# moire_v1_9-100mm.net
KiCad netlist of a schematic drawn in EAGLE
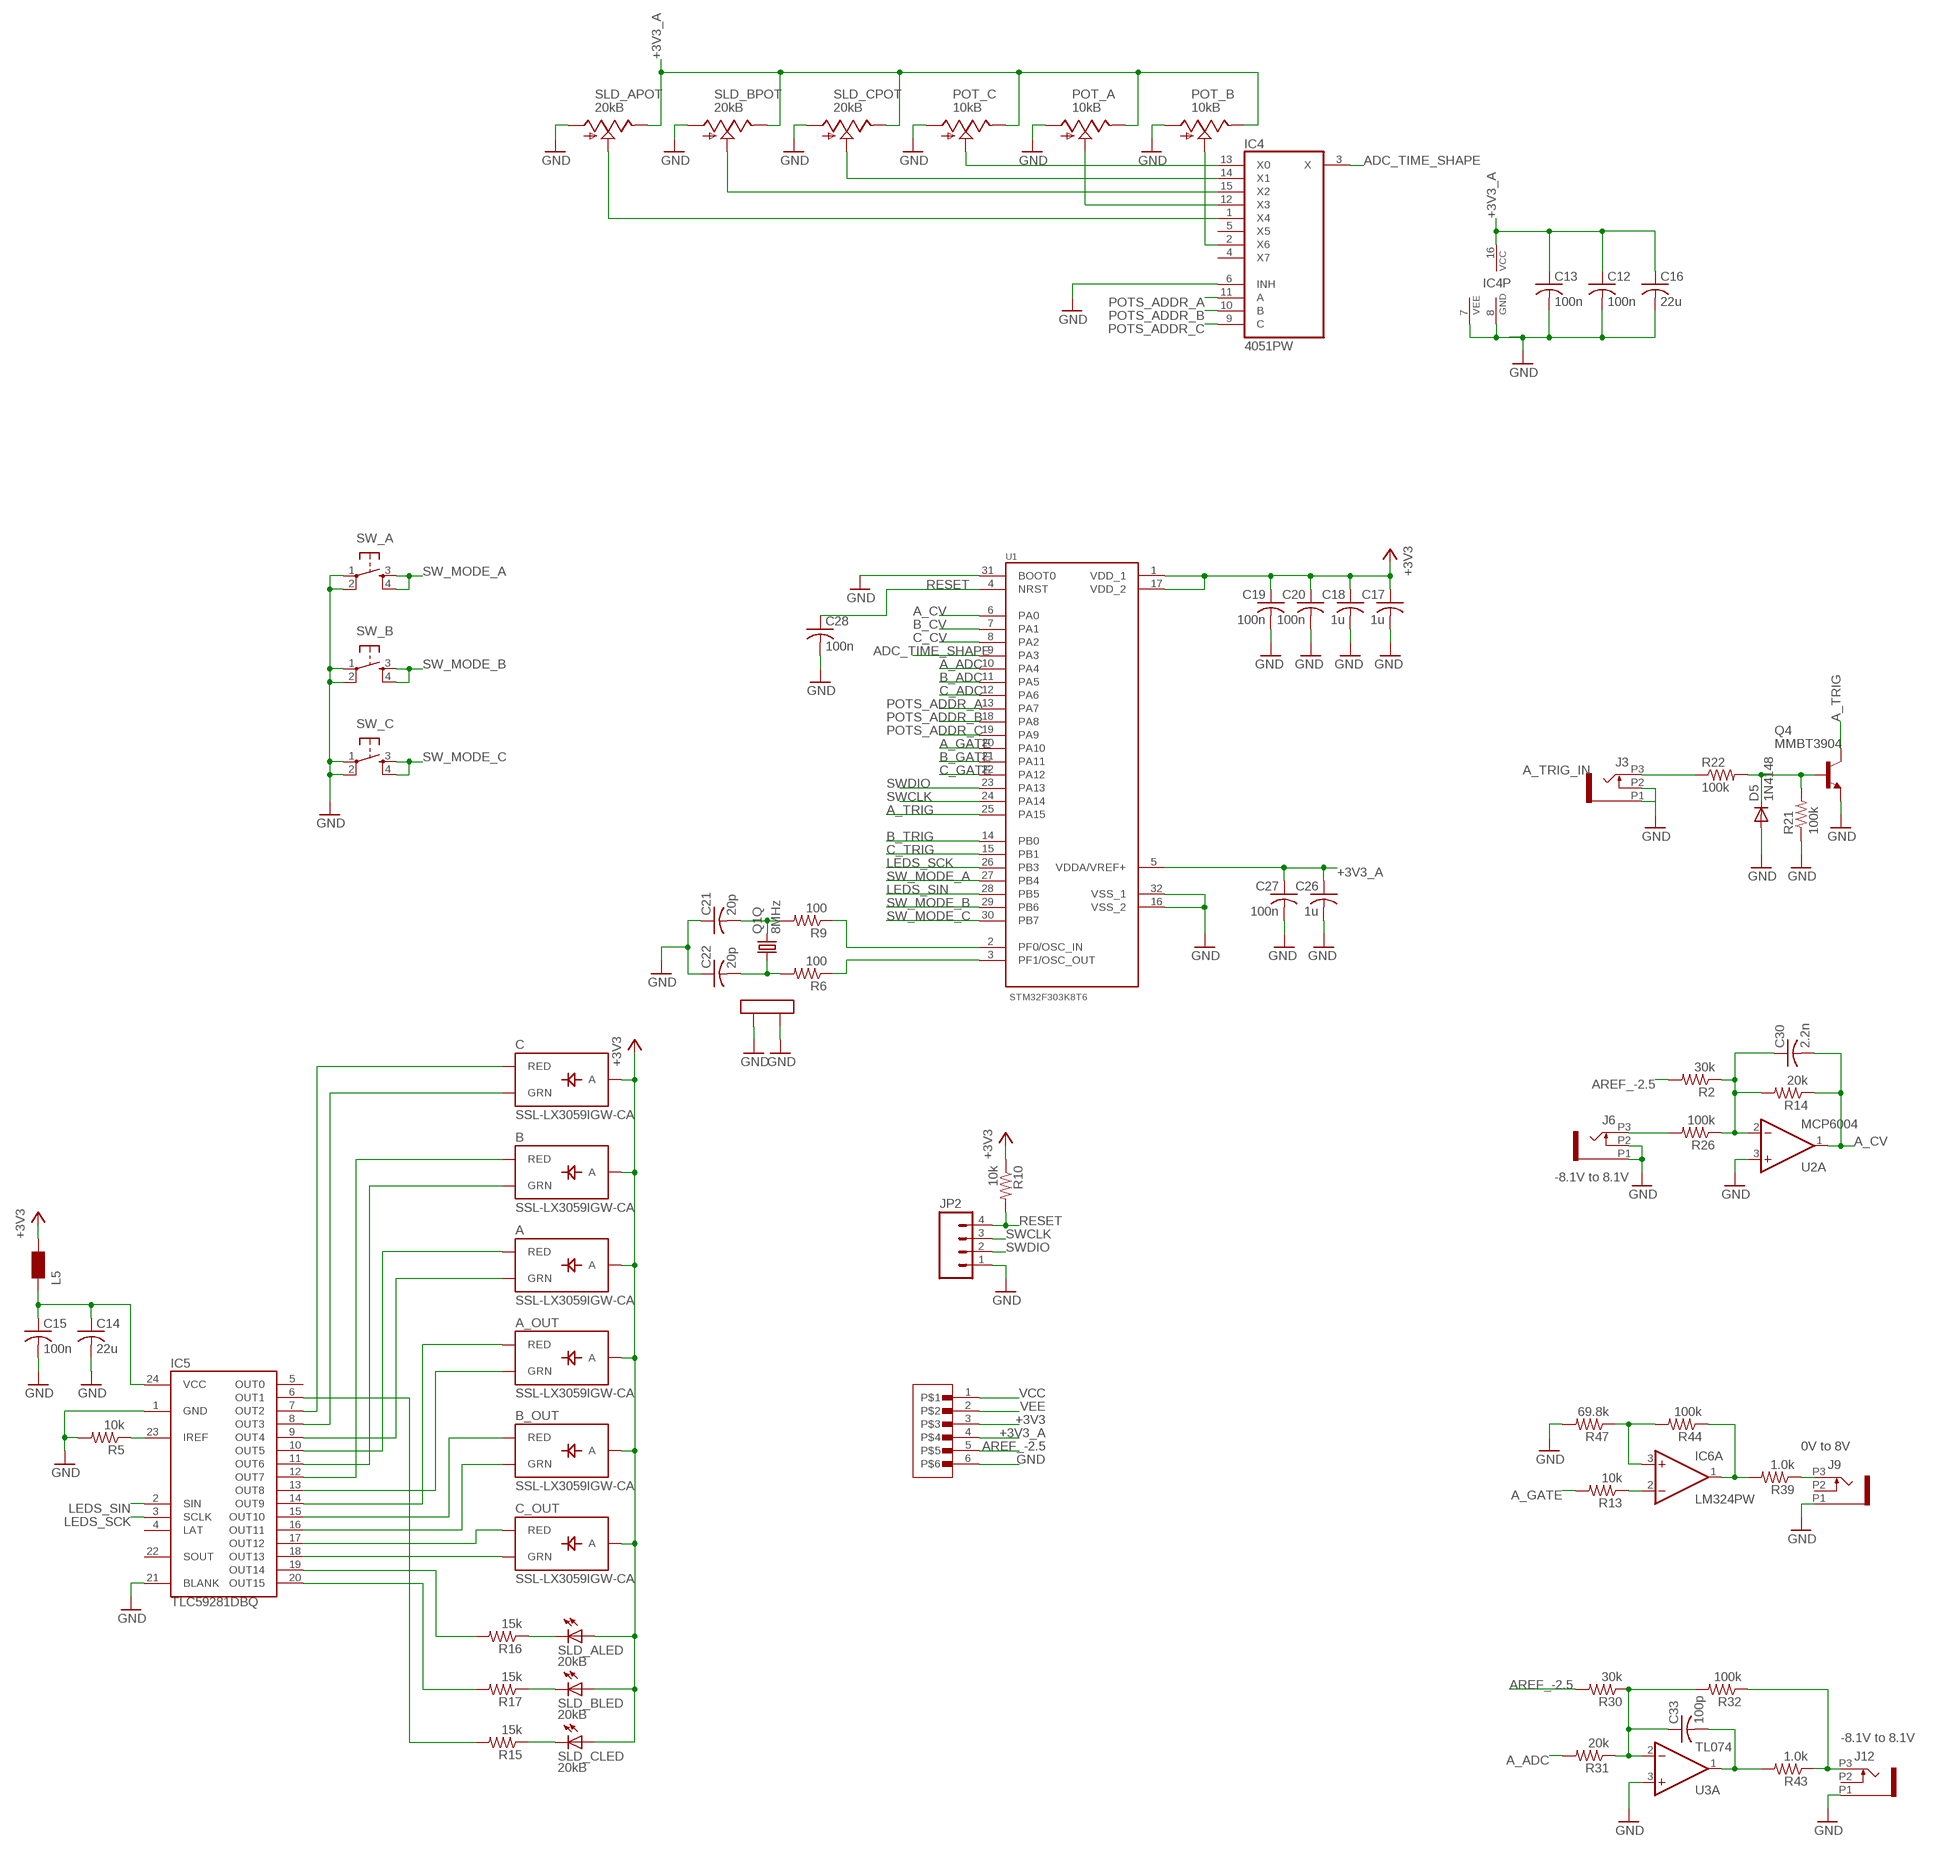
[diagram p0: schematic, sheet 1, part 1 of 2]
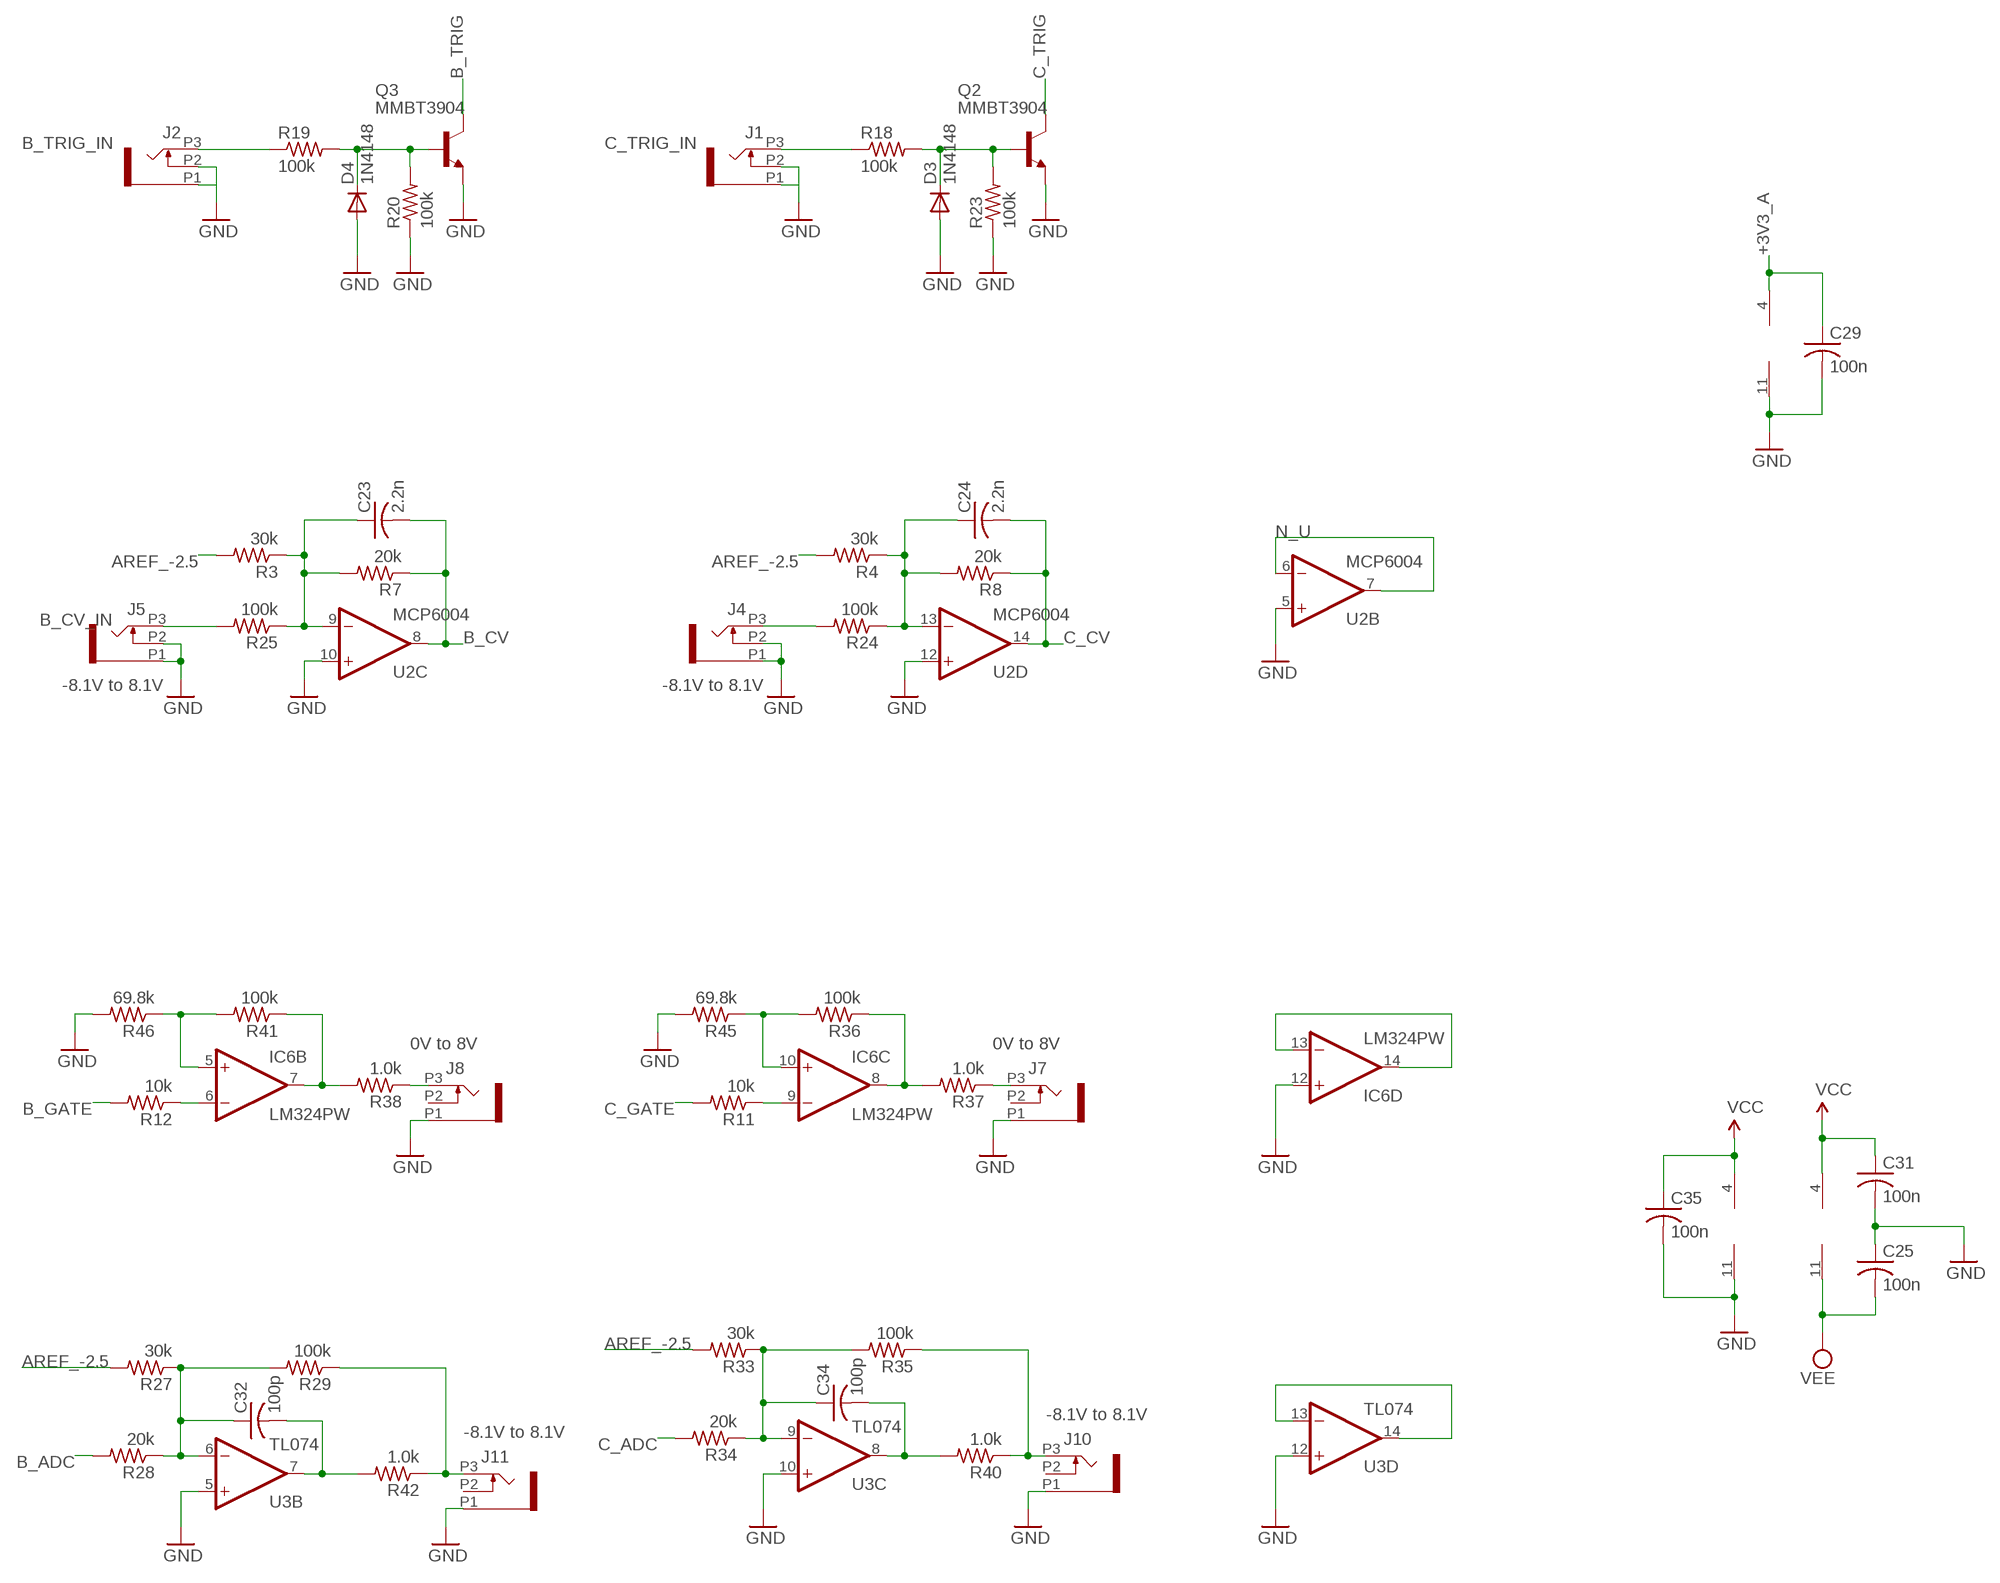
[diagram p1: schematic, sheet 1, part 2 of 2]
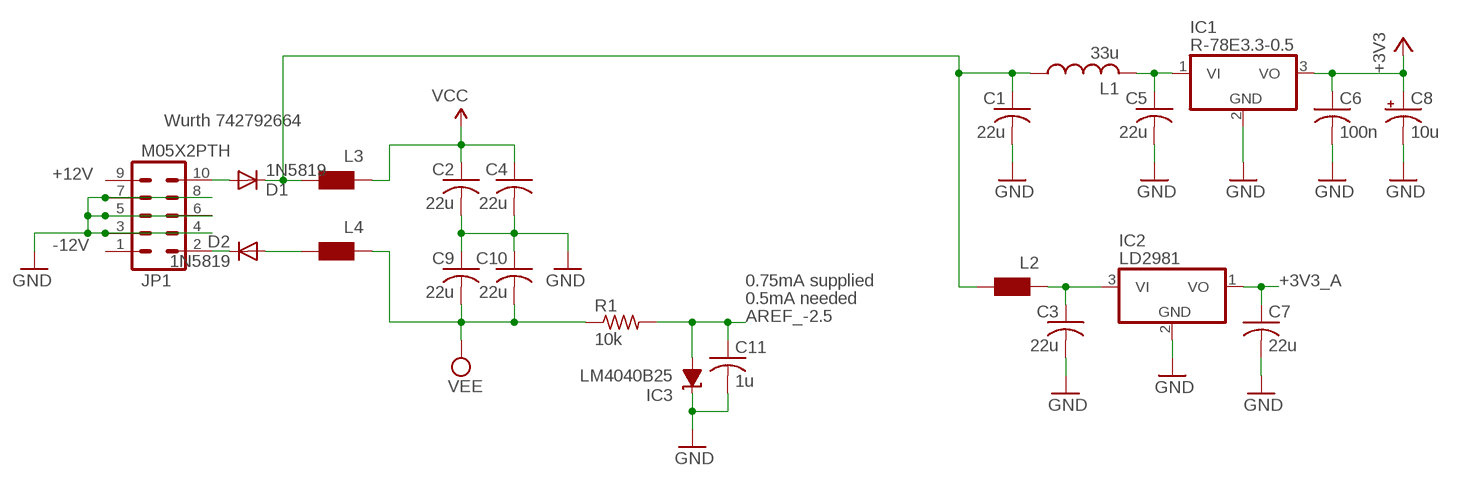
[diagram p2: schematic, sheet 2]

(export (version "E")
  (design (tool "Eeschema 10.0.6"))
  (components
    (comp (ref "C1")
      (value "22u")
      (footprint "eagle-import:RCL_C1206")
      (libsource (lib "eagle-import") (part "RCL_C-USC1206"))
    )
    (comp (ref "C2")
      (value "22u")
      (footprint "eagle-import:RCL_C1206")
      (libsource (lib "eagle-import") (part "RCL_C-USC1206"))
    )
    (comp (ref "C3")
      (value "22u")
      (footprint "eagle-import:RCL_C1206")
      (libsource (lib "eagle-import") (part "RCL_C-USC1206"))
    )
    (comp (ref "C4")
      (value "22u")
      (footprint "eagle-import:RCL_C1206")
      (libsource (lib "eagle-import") (part "RCL_C-USC1206"))
    )
    (comp (ref "C5")
      (value "22u")
      (footprint "eagle-import:RCL_C1206")
      (libsource (lib "eagle-import") (part "RCL_C-USC1206"))
    )
    (comp (ref "C6")
      (value "100n")
      (footprint "eagle-import:RCL_C0603")
      (libsource (lib "eagle-import") (part "RCL_C-USC0603"))
    )
    (comp (ref "C7")
      (value "22u")
      (footprint "eagle-import:RCL_C1206")
      (libsource (lib "eagle-import") (part "RCL_C-USC1206"))
    )
    (comp (ref "C8")
      (value "10u")
      (footprint "eagle-import:RCL_PANASONIC_A")
      (libsource (lib "eagle-import") (part "RCL_CPOL-USA"))
    )
    (comp (ref "C9")
      (value "22u")
      (footprint "eagle-import:RCL_C1206")
      (libsource (lib "eagle-import") (part "RCL_C-USC1206"))
    )
    (comp (ref "C10")
      (value "22u")
      (footprint "eagle-import:RCL_C1206")
      (libsource (lib "eagle-import") (part "RCL_C-USC1206"))
    )
    (comp (ref "C11")
      (value "1u")
      (footprint "eagle-import:RCL_C0603")
      (libsource (lib "eagle-import") (part "RCL_C-USC0603"))
    )
    (comp (ref "D1")
      (value "1N5819")
      (footprint "eagle-import:DIODE_SOD123")
      (libsource (lib "eagle-import") (part "DIODE_DIODE-SOD123"))
    )
    (comp (ref "D2")
      (value "1N5819")
      (footprint "eagle-import:DIODE_SOD123")
      (libsource (lib "eagle-import") (part "DIODE_DIODE-SOD123"))
    )
    (comp (ref "IC1")
      (value "R-78E3.3-0.5")
      (footprint "eagle-import:WE78")
      (libsource (lib "eagle-import") (part "WE173950378"))
    )
    (comp (ref "IC2")
      (value "LD2981")
      (footprint "eagle-import:SOT89")
      (libsource (lib "eagle-import") (part "LD2981ABU"))
    )
    (comp (ref "IC3")
      (value "LM4040B25")
      (footprint "eagle-import:DBZ_R-PDSO-G3")
      (libsource (lib "eagle-import") (part "LM4041DBZB12"))
    )
    (comp (ref "JP1")
      (value "M05X2PTH")
      (footprint "eagle-import:2X5-PTH")
      (libsource (lib "eagle-import") (part "M05X2PTH"))
    )
    (comp (ref "L1")
      (value "33u")
      (footprint "eagle-import:L2012C")
      (libsource (lib "eagle-import") (part "L-USL2012C"))
    )
    (comp (ref "L2")
      (value "WE-CBF_0603")
      (footprint "eagle-import:0603")
      (libsource (lib "eagle-import") (part "WE-CBF_0603"))
    )
    (comp (ref "L3")
      (value "WE-CBF_0603")
      (footprint "eagle-import:0603")
      (libsource (lib "eagle-import") (part "WE-CBF_0603"))
    )
    (comp (ref "L4")
      (value "WE-CBF_0603")
      (footprint "eagle-import:0603")
      (libsource (lib "eagle-import") (part "WE-CBF_0603"))
    )
    (comp (ref "R1")
      (value "10k")
      (footprint "eagle-import:RCL_R0603")
      (libsource (lib "eagle-import") (part "RCL_R-US_R0603"))
    )
    (comp (ref "A")
      (value "SSL-LX3059IGW-CA")
      (footprint "eagle-import:LED-BICOLOR-THROUGHHOLE-LUMEX")
      (libsource (lib "eagle-import") (part "LED-BICOLOR-THROUGHHOLE-CA"))
    )
    (comp (ref "A_OUT")
      (value "SSL-LX3059IGW-CA")
      (footprint "eagle-import:LED-BICOLOR-THROUGHHOLE-LUMEX")
      (libsource (lib "eagle-import") (part "LED-BICOLOR-THROUGHHOLE-CA"))
    )
    (comp (ref "B")
      (value "SSL-LX3059IGW-CA")
      (footprint "eagle-import:LED-BICOLOR-THROUGHHOLE-LUMEX")
      (libsource (lib "eagle-import") (part "LED-BICOLOR-THROUGHHOLE-CA"))
    )
    (comp (ref "B_OUT")
      (value "SSL-LX3059IGW-CA")
      (footprint "eagle-import:LED-BICOLOR-THROUGHHOLE-LUMEX")
      (libsource (lib "eagle-import") (part "LED-BICOLOR-THROUGHHOLE-CA"))
    )
    (comp (ref "C")
      (value "SSL-LX3059IGW-CA")
      (footprint "eagle-import:LED-BICOLOR-THROUGHHOLE-LUMEX")
      (libsource (lib "eagle-import") (part "LED-BICOLOR-THROUGHHOLE-CA"))
    )
    (comp (ref "C12")
      (value "100n")
      (footprint "eagle-import:RCL_C0603")
      (libsource (lib "eagle-import") (part "RCL_C-USC0603"))
    )
    (comp (ref "C13")
      (value "100n")
      (footprint "eagle-import:RCL_C0603")
      (libsource (lib "eagle-import") (part "RCL_C-USC0603"))
    )
    (comp (ref "C14")
      (value "22u")
      (footprint "eagle-import:RCL_C1206")
      (libsource (lib "eagle-import") (part "RCL_C-USC1206"))
    )
    (comp (ref "C15")
      (value "100n")
      (footprint "eagle-import:RCL_C0603")
      (libsource (lib "eagle-import") (part "RCL_C-USC0603"))
    )
    (comp (ref "C16")
      (value "22u")
      (footprint "eagle-import:RCL_C1206")
      (libsource (lib "eagle-import") (part "RCL_C-USC1206"))
    )
    (comp (ref "C17")
      (value "1u")
      (footprint "eagle-import:RCL_C0603")
      (libsource (lib "eagle-import") (part "RCL_C-USC0603"))
    )
    (comp (ref "C18")
      (value "1u")
      (footprint "eagle-import:RCL_C0603")
      (libsource (lib "eagle-import") (part "RCL_C-USC0603"))
    )
    (comp (ref "C19")
      (value "100n")
      (footprint "eagle-import:RCL_C0603")
      (libsource (lib "eagle-import") (part "RCL_C-USC0603"))
    )
    (comp (ref "C20")
      (value "100n")
      (footprint "eagle-import:RCL_C0603")
      (libsource (lib "eagle-import") (part "RCL_C-USC0603"))
    )
    (comp (ref "C21")
      (value "20p")
      (footprint "eagle-import:RCL_C0603")
      (libsource (lib "eagle-import") (part "RCL_C-USC0603"))
    )
    (comp (ref "C22")
      (value "20p")
      (footprint "eagle-import:RCL_C0603")
      (libsource (lib "eagle-import") (part "RCL_C-USC0603"))
    )
    (comp (ref "C23")
      (value "2.2n")
      (footprint "eagle-import:RCL_C0603")
      (libsource (lib "eagle-import") (part "RCL_C-USC0603"))
    )
    (comp (ref "C24")
      (value "2.2n")
      (footprint "eagle-import:RCL_C0603")
      (libsource (lib "eagle-import") (part "RCL_C-USC0603"))
    )
    (comp (ref "C25")
      (value "100n")
      (footprint "eagle-import:RCL_C0603")
      (libsource (lib "eagle-import") (part "RCL_C-USC0603"))
    )
    (comp (ref "C26")
      (value "1u")
      (footprint "eagle-import:RCL_C0603")
      (libsource (lib "eagle-import") (part "RCL_C-USC0603"))
    )
    (comp (ref "C27")
      (value "100n")
      (footprint "eagle-import:RCL_C0603")
      (libsource (lib "eagle-import") (part "RCL_C-USC0603"))
    )
    (comp (ref "C28")
      (value "100n")
      (footprint "eagle-import:RCL_C0603")
      (libsource (lib "eagle-import") (part "RCL_C-USC0603"))
    )
    (comp (ref "C29")
      (value "100n")
      (footprint "eagle-import:RCL_C0603")
      (libsource (lib "eagle-import") (part "RCL_C-USC0603"))
    )
    (comp (ref "C30")
      (value "2.2n")
      (footprint "eagle-import:RCL_C0603")
      (libsource (lib "eagle-import") (part "RCL_C-USC0603"))
    )
    (comp (ref "C31")
      (value "100n")
      (footprint "eagle-import:RCL_C0603")
      (libsource (lib "eagle-import") (part "RCL_C-USC0603"))
    )
    (comp (ref "C32")
      (value "100p")
      (footprint "eagle-import:RCL_C0603")
      (libsource (lib "eagle-import") (part "RCL_C-USC0603"))
    )
    (comp (ref "C33")
      (value "100p")
      (footprint "eagle-import:RCL_C0603")
      (libsource (lib "eagle-import") (part "RCL_C-USC0603"))
    )
    (comp (ref "C34")
      (value "100p")
      (footprint "eagle-import:RCL_C0603")
      (libsource (lib "eagle-import") (part "RCL_C-USC0603"))
    )
    (comp (ref "C35")
      (value "100n")
      (footprint "eagle-import:RCL_C0603")
      (libsource (lib "eagle-import") (part "RCL_C-USC0603"))
    )
    (comp (ref "C_OUT")
      (value "SSL-LX3059IGW-CA")
      (footprint "eagle-import:LED-BICOLOR-THROUGHHOLE-LUMEX")
      (libsource (lib "eagle-import") (part "LED-BICOLOR-THROUGHHOLE-CA"))
    )
    (comp (ref "D3")
      (value "1N4148")
      (footprint "eagle-import:DIODE_SOD523")
      (libsource (lib "eagle-import") (part "DIODE_DIODE-SOD523"))
    )
    (comp (ref "D4")
      (value "1N4148")
      (footprint "eagle-import:DIODE_SOD523")
      (libsource (lib "eagle-import") (part "DIODE_DIODE-SOD523"))
    )
    (comp (ref "D5")
      (value "1N4148")
      (footprint "eagle-import:DIODE_SOD523")
      (libsource (lib "eagle-import") (part "DIODE_DIODE-SOD523"))
    )
    (comp (ref "IC4")
      (value "4051PW")
      (footprint "eagle-import:TSSOP16_065")
      (libsource (lib "eagle-import") (part "4051PW"))
    )
    (comp (ref "IC5")
      (value "TLC59281DBQ")
      (footprint "eagle-import:TSSOP24_0635")
      (libsource (lib "eagle-import") (part "TLC59281DBQ"))
    )
    (comp (ref "IC6")
      (value "LM324PW")
      (footprint "eagle-import:TSSOP14_065")
      (libsource (lib "eagle-import") (part "TL074PW"))
    )
    (comp (ref "J1")
      (value "PJ301_THONKICONN6")
      (footprint "eagle-import:WQP_PJ_301M6")
      (libsource (lib "eagle-import") (part "PJ301_THONKICONN6"))
    )
    (comp (ref "J2")
      (value "PJ301_THONKICONN6")
      (footprint "eagle-import:WQP_PJ_301M6")
      (libsource (lib "eagle-import") (part "PJ301_THONKICONN6"))
    )
    (comp (ref "J3")
      (value "PJ301_THONKICONN6")
      (footprint "eagle-import:WQP_PJ_301M6")
      (libsource (lib "eagle-import") (part "PJ301_THONKICONN6"))
    )
    (comp (ref "J4")
      (value "PJ301_THONKICONN6")
      (footprint "eagle-import:WQP_PJ_301M6")
      (libsource (lib "eagle-import") (part "PJ301_THONKICONN6"))
    )
    (comp (ref "J5")
      (value "PJ301_THONKICONN6")
      (footprint "eagle-import:WQP_PJ_301M6")
      (libsource (lib "eagle-import") (part "PJ301_THONKICONN6"))
    )
    (comp (ref "J6")
      (value "PJ301_THONKICONN6")
      (footprint "eagle-import:WQP_PJ_301M6")
      (libsource (lib "eagle-import") (part "PJ301_THONKICONN6"))
    )
    (comp (ref "J7")
      (value "PJ301_THONKICONN6")
      (footprint "eagle-import:WQP_PJ_301M6")
      (libsource (lib "eagle-import") (part "PJ301_THONKICONN6"))
    )
    (comp (ref "J8")
      (value "PJ301_THONKICONN6")
      (footprint "eagle-import:WQP_PJ_301M6")
      (libsource (lib "eagle-import") (part "PJ301_THONKICONN6"))
    )
    (comp (ref "J9")
      (value "PJ301_THONKICONN6")
      (footprint "eagle-import:WQP_PJ_301M6")
      (libsource (lib "eagle-import") (part "PJ301_THONKICONN6"))
    )
    (comp (ref "J10")
      (value "PJ301_THONKICONN6")
      (footprint "eagle-import:WQP_PJ_301M6")
      (libsource (lib "eagle-import") (part "PJ301_THONKICONN6"))
    )
    (comp (ref "J11")
      (value "PJ301_THONKICONN6")
      (footprint "eagle-import:WQP_PJ_301M6")
      (libsource (lib "eagle-import") (part "PJ301_THONKICONN6"))
    )
    (comp (ref "J12")
      (value "PJ301_THONKICONN6")
      (footprint "eagle-import:WQP_PJ_301M6")
      (libsource (lib "eagle-import") (part "PJ301_THONKICONN6"))
    )
    (comp (ref "JP2")
      (value "M04PTH")
      (footprint "eagle-import:1X04")
      (libsource (lib "eagle-import") (part "M04PTH"))
    )
    (comp (ref "L5")
      (value "WE-CBF_0603")
      (footprint "eagle-import:0603")
      (libsource (lib "eagle-import") (part "WE-CBF_0603"))
    )
    (comp (ref "POT_A")
      (value "10kB")
      (footprint "eagle-import:ALPS_POT_VERTICAL")
      (libsource (lib "eagle-import") (part "POT_USVERTICAL"))
    )
    (comp (ref "POT_B")
      (value "10kB")
      (footprint "eagle-import:ALPS_POT_VERTICAL")
      (libsource (lib "eagle-import") (part "POT_USVERTICAL"))
    )
    (comp (ref "POT_C")
      (value "10kB")
      (footprint "eagle-import:ALPS_POT_VERTICAL")
      (libsource (lib "eagle-import") (part "POT_USVERTICAL"))
    )
    (comp (ref "Q1")
      (value "8MHz")
      (footprint "eagle-import:CTS406")
      (libsource (lib "eagle-import") (part "CRYSTAL"))
    )
    (comp (ref "Q2")
      (value "MMBT3904")
      (footprint "eagle-import:SOT23-BEC")
      (libsource (lib "eagle-import") (part "-NPN-SOT23-BECMMBT3904LT1"))
    )
    (comp (ref "Q3")
      (value "MMBT3904")
      (footprint "eagle-import:SOT23-BEC")
      (libsource (lib "eagle-import") (part "-NPN-SOT23-BECMMBT3904LT1"))
    )
    (comp (ref "Q4")
      (value "MMBT3904")
      (footprint "eagle-import:SOT23-BEC")
      (libsource (lib "eagle-import") (part "-NPN-SOT23-BECMMBT3904LT1"))
    )
    (comp (ref "R2")
      (value "30k")
      (footprint "eagle-import:RCL_R0603")
      (libsource (lib "eagle-import") (part "RCL_R-US_R0603"))
    )
    (comp (ref "R3")
      (value "30k")
      (footprint "eagle-import:RCL_R0603")
      (libsource (lib "eagle-import") (part "RCL_R-US_R0603"))
    )
    (comp (ref "R4")
      (value "30k")
      (footprint "eagle-import:RCL_R0603")
      (libsource (lib "eagle-import") (part "RCL_R-US_R0603"))
    )
    (comp (ref "R5")
      (value "10k")
      (footprint "eagle-import:RCL_R0603")
      (libsource (lib "eagle-import") (part "RCL_R-US_R0603"))
    )
    (comp (ref "R6")
      (value "100")
      (footprint "eagle-import:RCL_R0603")
      (libsource (lib "eagle-import") (part "RCL_R-US_R0603"))
    )
    (comp (ref "R7")
      (value "20k")
      (footprint "eagle-import:RCL_R0603")
      (libsource (lib "eagle-import") (part "RCL_R-US_R0603"))
    )
    (comp (ref "R8")
      (value "20k")
      (footprint "eagle-import:RCL_R0603")
      (libsource (lib "eagle-import") (part "RCL_R-US_R0603"))
    )
    (comp (ref "R9")
      (value "100")
      (footprint "eagle-import:RCL_R0603")
      (libsource (lib "eagle-import") (part "RCL_R-US_R0603"))
    )
    (comp (ref "R10")
      (value "10k")
      (footprint "eagle-import:RCL_R0603")
      (libsource (lib "eagle-import") (part "RCL_R-US_R0603"))
    )
    (comp (ref "R11")
      (value "10k")
      (footprint "eagle-import:RCL_R0603")
      (libsource (lib "eagle-import") (part "RCL_R-US_R0603"))
    )
    (comp (ref "R12")
      (value "10k")
      (footprint "eagle-import:RCL_R0603")
      (libsource (lib "eagle-import") (part "RCL_R-US_R0603"))
    )
    (comp (ref "R13")
      (value "10k")
      (footprint "eagle-import:RCL_R0603")
      (libsource (lib "eagle-import") (part "RCL_R-US_R0603"))
    )
    (comp (ref "R14")
      (value "20k")
      (footprint "eagle-import:RCL_R0603")
      (libsource (lib "eagle-import") (part "RCL_R-US_R0603"))
    )
    (comp (ref "R15")
      (value "15k")
      (footprint "eagle-import:RCL_R0603")
      (libsource (lib "eagle-import") (part "RCL_R-US_R0603"))
    )
    (comp (ref "R16")
      (value "15k")
      (footprint "eagle-import:RCL_R0603")
      (libsource (lib "eagle-import") (part "RCL_R-US_R0603"))
    )
    (comp (ref "R17")
      (value "15k")
      (footprint "eagle-import:RCL_R0603")
      (libsource (lib "eagle-import") (part "RCL_R-US_R0603"))
    )
    (comp (ref "R18")
      (value "100k")
      (footprint "eagle-import:RCL_R0603")
      (libsource (lib "eagle-import") (part "RCL_R-US_R0603"))
    )
    (comp (ref "R19")
      (value "100k")
      (footprint "eagle-import:RCL_R0603")
      (libsource (lib "eagle-import") (part "RCL_R-US_R0603"))
    )
    (comp (ref "R20")
      (value "100k")
      (footprint "eagle-import:RCL_R0603")
      (libsource (lib "eagle-import") (part "RCL_R-US_R0603"))
    )
    (comp (ref "R21")
      (value "100k")
      (footprint "eagle-import:RCL_R0603")
      (libsource (lib "eagle-import") (part "RCL_R-US_R0603"))
    )
    (comp (ref "R22")
      (value "100k")
      (footprint "eagle-import:RCL_R0603")
      (libsource (lib "eagle-import") (part "RCL_R-US_R0603"))
    )
    (comp (ref "R23")
      (value "100k")
      (footprint "eagle-import:RCL_R0603")
      (libsource (lib "eagle-import") (part "RCL_R-US_R0603"))
    )
    (comp (ref "R24")
      (value "100k")
      (footprint "eagle-import:RCL_R0603")
      (libsource (lib "eagle-import") (part "RCL_R-US_R0603"))
    )
    (comp (ref "R25")
      (value "100k")
      (footprint "eagle-import:RCL_R0603")
      (libsource (lib "eagle-import") (part "RCL_R-US_R0603"))
    )
    (comp (ref "R26")
      (value "100k")
      (footprint "eagle-import:RCL_R0603")
      (libsource (lib "eagle-import") (part "RCL_R-US_R0603"))
    )
    (comp (ref "R27")
      (value "30k")
      (footprint "eagle-import:RCL_R0603")
      (libsource (lib "eagle-import") (part "RCL_R-US_R0603"))
    )
    (comp (ref "R28")
      (value "20k")
      (footprint "eagle-import:RCL_R0603")
      (libsource (lib "eagle-import") (part "RCL_R-US_R0603"))
    )
    (comp (ref "R29")
      (value "100k")
      (footprint "eagle-import:RCL_R0603")
      (libsource (lib "eagle-import") (part "RCL_R-US_R0603"))
    )
    (comp (ref "R30")
      (value "30k")
      (footprint "eagle-import:RCL_R0603")
      (libsource (lib "eagle-import") (part "RCL_R-US_R0603"))
    )
    (comp (ref "R31")
      (value "20k")
      (footprint "eagle-import:RCL_R0603")
      (libsource (lib "eagle-import") (part "RCL_R-US_R0603"))
    )
    (comp (ref "R32")
      (value "100k")
      (footprint "eagle-import:RCL_R0603")
      (libsource (lib "eagle-import") (part "RCL_R-US_R0603"))
    )
    (comp (ref "R33")
      (value "30k")
      (footprint "eagle-import:RCL_R0603")
      (libsource (lib "eagle-import") (part "RCL_R-US_R0603"))
    )
    (comp (ref "R34")
      (value "20k")
      (footprint "eagle-import:RCL_R0603")
      (libsource (lib "eagle-import") (part "RCL_R-US_R0603"))
    )
    (comp (ref "R35")
      (value "100k")
      (footprint "eagle-import:RCL_R0603")
      (libsource (lib "eagle-import") (part "RCL_R-US_R0603"))
    )
    (comp (ref "R36")
      (value "100k")
      (footprint "eagle-import:RCL_R0603")
      (libsource (lib "eagle-import") (part "RCL_R-US_R0603"))
    )
    (comp (ref "R37")
      (value "1.0k")
      (footprint "eagle-import:RCL_R0603")
      (libsource (lib "eagle-import") (part "RCL_R-US_R0603"))
    )
    (comp (ref "R38")
      (value "1.0k")
      (footprint "eagle-import:RCL_R0603")
      (libsource (lib "eagle-import") (part "RCL_R-US_R0603"))
    )
    (comp (ref "R39")
      (value "1.0k")
      (footprint "eagle-import:RCL_R0603")
      (libsource (lib "eagle-import") (part "RCL_R-US_R0603"))
    )
    (comp (ref "R40")
      (value "1.0k")
      (footprint "eagle-import:RCL_R0603")
      (libsource (lib "eagle-import") (part "RCL_R-US_R0603"))
    )
    (comp (ref "R41")
      (value "100k")
      (footprint "eagle-import:RCL_R0603")
      (libsource (lib "eagle-import") (part "RCL_R-US_R0603"))
    )
    (comp (ref "R42")
      (value "1.0k")
      (footprint "eagle-import:RCL_R0603")
      (libsource (lib "eagle-import") (part "RCL_R-US_R0603"))
    )
    (comp (ref "R43")
      (value "1.0k")
      (footprint "eagle-import:RCL_R0603")
      (libsource (lib "eagle-import") (part "RCL_R-US_R0603"))
    )
    (comp (ref "R44")
      (value "100k")
      (footprint "eagle-import:RCL_R0603")
      (libsource (lib "eagle-import") (part "RCL_R-US_R0603"))
    )
    (comp (ref "R45")
      (value "69.8k")
      (footprint "eagle-import:RCL_R0603")
      (libsource (lib "eagle-import") (part "RCL_R-US_R0603"))
    )
    (comp (ref "R46")
      (value "69.8k")
      (footprint "eagle-import:RCL_R0603")
      (libsource (lib "eagle-import") (part "RCL_R-US_R0603"))
    )
    (comp (ref "R47")
      (value "69.8k")
      (footprint "eagle-import:RCL_R0603")
      (libsource (lib "eagle-import") (part "RCL_R-US_R0603"))
    )
    (comp (ref "SLD_A")
      (value "20kB")
      (footprint "eagle-import:BOURNS_SLIDER")
      (libsource (lib "eagle-import") (part "BOURNS_SLIDER"))
    )
    (comp (ref "SLD_B")
      (value "20kB")
      (footprint "eagle-import:BOURNS_SLIDER")
      (libsource (lib "eagle-import") (part "BOURNS_SLIDER"))
    )
    (comp (ref "SLD_C")
      (value "20kB")
      (footprint "eagle-import:BOURNS_SLIDER")
      (libsource (lib "eagle-import") (part "BOURNS_SLIDER"))
    )
    (comp (ref "SW_A")
      (value "TAC_SWITCHPTH")
      (footprint "eagle-import:TACTILE-PTH")
      (libsource (lib "eagle-import") (part "TAC_SWITCHPTH"))
    )
    (comp (ref "SW_B")
      (value "TAC_SWITCHPTH")
      (footprint "eagle-import:TACTILE-PTH")
      (libsource (lib "eagle-import") (part "TAC_SWITCHPTH"))
    )
    (comp (ref "SW_C")
      (value "TAC_SWITCHPTH")
      (footprint "eagle-import:TACTILE-PTH")
      (libsource (lib "eagle-import") (part "TAC_SWITCHPTH"))
    )
    (comp (ref "U$1")
      (value "1X6-SMD-TESTPAD")
      (footprint "eagle-import:6X1-SMD-TESTPAD")
      (libsource (lib "eagle-import") (part "1X6-SMD-TESTPAD"))
    )
    (comp (ref "U1")
      (value "STM32F303K8T6")
      (footprint "eagle-import:QFP80P900X900X160-32N")
      (fields (field (name "MF") "STMicroelectronics"))
      (libsource (lib "eagle-import") (part "STM32F303K8T6"))
    )
    (comp (ref "U2")
      (value "MCP6004")
      (footprint "eagle-import:SO14")
      (libsource (lib "eagle-import") (part "MCP6004_SMD"))
    )
    (comp (ref "U3")
      (value "TL074")
      (footprint "eagle-import:SO14")
      (libsource (lib "eagle-import") (part "TL074_SMD"))
    )
  )
  (nets
    (net (code "1") (name "+3V3") (class "Default")
      (node (ref "A") (pin "A") (pinfunction "A_A") (pintype "bidirectional"))
      (node (ref "A_OUT") (pin "A") (pinfunction "A_A") (pintype "bidirectional"))
      (node (ref "B") (pin "A") (pinfunction "A_A") (pintype "bidirectional"))
      (node (ref "B_OUT") (pin "A") (pinfunction "A_A") (pintype "bidirectional"))
      (node (ref "C") (pin "A") (pinfunction "A_A") (pintype "bidirectional"))
      (node (ref "C17") (pin "1") (pinfunction "1_1") (pintype "passive"))
      (node (ref "C18") (pin "1") (pinfunction "1_1") (pintype "passive"))
      (node (ref "C19") (pin "1") (pinfunction "1_1") (pintype "passive"))
      (node (ref "C20") (pin "1") (pinfunction "1_1") (pintype "passive"))
      (node (ref "C6") (pin "1") (pinfunction "1_1") (pintype "passive"))
      (node (ref "C8") (pin "+") (pinfunction "+_+") (pintype "passive"))
      (node (ref "C_OUT") (pin "A") (pinfunction "A_A") (pintype "bidirectional"))
      (node (ref "IC1") (pin "3") (pinfunction "VO_3") (pintype "passive"))
      (node (ref "L5") (pin "2") (pinfunction "2_2") (pintype "passive"))
      (node (ref "R10") (pin "1") (pinfunction "1_1") (pintype "passive"))
      (node (ref "SLD_A") (pin "B") (pinfunction "A_B") (pintype "passive"))
      (node (ref "SLD_B") (pin "B") (pinfunction "A_B") (pintype "passive"))
      (node (ref "SLD_C") (pin "B") (pinfunction "A_B") (pintype "passive"))
      (node (ref "U$1") (pin "3") (pinfunction "P$3_3") (pintype "bidirectional"))
      (node (ref "U1") (pin "1") (pinfunction "VDD_1_1") (pintype "power_in"))
      (node (ref "U1") (pin "17") (pinfunction "VDD_2_17") (pintype "power_in"))
    )
    (net (code "2") (name "+3V3_A") (class "Default")
      (node (ref "C12") (pin "1") (pinfunction "1_1") (pintype "passive"))
      (node (ref "C13") (pin "1") (pinfunction "1_1") (pintype "passive"))
      (node (ref "C16") (pin "1") (pinfunction "1_1") (pintype "passive"))
      (node (ref "C26") (pin "1") (pinfunction "1_1") (pintype "passive"))
      (node (ref "C27") (pin "1") (pinfunction "1_1") (pintype "passive"))
      (node (ref "C29") (pin "1") (pinfunction "1_1") (pintype "passive"))
      (node (ref "C7") (pin "1") (pinfunction "1_1") (pintype "passive"))
      (node (ref "IC2") (pin "1") (pinfunction "VO_1") (pintype "passive"))
      (node (ref "IC4") (pin "16") (pinfunction "VCC_16") (pintype "power_in"))
      (node (ref "POT_A") (pin "P$1") (pinfunction "E_P$1") (pintype "passive"))
      (node (ref "POT_B") (pin "P$1") (pinfunction "E_P$1") (pintype "passive"))
      (node (ref "POT_C") (pin "P$1") (pinfunction "E_P$1") (pintype "passive"))
      (node (ref "SLD_A") (pin "3") (pinfunction "E_3") (pintype "passive"))
      (node (ref "SLD_B") (pin "3") (pinfunction "E_3") (pintype "passive"))
      (node (ref "SLD_C") (pin "3") (pinfunction "E_3") (pintype "passive"))
      (node (ref "U$1") (pin "4") (pinfunction "P$4_4") (pintype "bidirectional"))
      (node (ref "U1") (pin "5") (pinfunction "VDDA/VREF+_5") (pintype "power_in"))
      (node (ref "U2") (pin "4") (pinfunction "V+_4") (pintype "power_in"))
    )
    (net (code "3") (name "+12V") (class "Default")
      (node (ref "D1") (pin "A") (pinfunction "A_A") (pintype "passive"))
      (node (ref "JP1") (pin "10") (pinfunction "10_10") (pintype "passive"))
      (node (ref "JP1") (pin "9") (pinfunction "9_9") (pintype "passive"))
    )
    (net (code "4") (name "-12V") (class "Default")
      (node (ref "D2") (pin "C") (pinfunction "C_C") (pintype "passive"))
      (node (ref "JP1") (pin "1") (pinfunction "1_1") (pintype "passive"))
      (node (ref "JP1") (pin "2") (pinfunction "2_2") (pintype "passive"))
    )
    (net (code "5") (name "ADC_TIME_SHAPE") (class "Default")
      (node (ref "IC4") (pin "3") (pinfunction "X_3") (pintype "bidirectional"))
      (node (ref "U1") (pin "9") (pinfunction "PA3_9") (pintype "bidirectional"))
    )
    (net (code "6") (name "AREF_-2.5") (class "Default")
      (node (ref "C11") (pin "1") (pinfunction "1_1") (pintype "passive"))
      (node (ref "IC3") (pin "2") (pinfunction "A_2") (pintype "passive"))
      (node (ref "R1") (pin "2") (pinfunction "2_2") (pintype "passive"))
      (node (ref "R2") (pin "2") (pinfunction "2_2") (pintype "passive"))
      (node (ref "R27") (pin "2") (pinfunction "2_2") (pintype "passive"))
      (node (ref "R3") (pin "2") (pinfunction "2_2") (pintype "passive"))
      (node (ref "R30") (pin "2") (pinfunction "2_2") (pintype "passive"))
      (node (ref "R33") (pin "2") (pinfunction "2_2") (pintype "passive"))
      (node (ref "R4") (pin "2") (pinfunction "2_2") (pintype "passive"))
      (node (ref "U$1") (pin "5") (pinfunction "P$5_5") (pintype "bidirectional"))
    )
    (net (code "7") (name "A_ADC") (class "Default")
      (node (ref "R31") (pin "2") (pinfunction "2_2") (pintype "passive"))
      (node (ref "U1") (pin "10") (pinfunction "PA4_10") (pintype "bidirectional"))
    )
    (net (code "8") (name "A_CV") (class "Default")
      (node (ref "C30") (pin "2") (pinfunction "2_2") (pintype "passive"))
      (node (ref "R14") (pin "1") (pinfunction "1_1") (pintype "passive"))
      (node (ref "U1") (pin "6") (pinfunction "PA0_6") (pintype "bidirectional"))
      (node (ref "U2") (pin "1") (pinfunction "OUT_1") (pintype "output"))
    )
    (net (code "9") (name "A_GATE") (class "Default")
      (node (ref "R13") (pin "2") (pinfunction "2_2") (pintype "passive"))
      (node (ref "U1") (pin "20") (pinfunction "PA10_20") (pintype "bidirectional"))
    )
    (net (code "10") (name "A_TRIG") (class "Default")
      (node (ref "Q4") (pin "C") (pinfunction "C_C") (pintype "passive"))
      (node (ref "U1") (pin "25") (pinfunction "PA15_25") (pintype "bidirectional"))
    )
    (net (code "11") (name "A_TRIG_IN") (class "Default")
      (node (ref "J3") (pin "P3") (pinfunction "3_P3") (pintype "passive"))
      (node (ref "R22") (pin "1") (pinfunction "1_1") (pintype "passive"))
    )
    (net (code "12") (name "B_ADC") (class "Default")
      (node (ref "R28") (pin "2") (pinfunction "2_2") (pintype "passive"))
      (node (ref "U1") (pin "11") (pinfunction "PA5_11") (pintype "bidirectional"))
    )
    (net (code "13") (name "B_CV") (class "Default")
      (node (ref "C23") (pin "2") (pinfunction "2_2") (pintype "passive"))
      (node (ref "R7") (pin "1") (pinfunction "1_1") (pintype "passive"))
      (node (ref "U1") (pin "7") (pinfunction "PA1_7") (pintype "bidirectional"))
      (node (ref "U2") (pin "8") (pinfunction "OUT_8") (pintype "output"))
    )
    (net (code "14") (name "B_CV_IN") (class "Default")
      (node (ref "J5") (pin "P3") (pinfunction "3_P3") (pintype "passive"))
      (node (ref "R25") (pin "2") (pinfunction "2_2") (pintype "passive"))
    )
    (net (code "15") (name "B_GATE") (class "Default")
      (node (ref "R12") (pin "2") (pinfunction "2_2") (pintype "passive"))
      (node (ref "U1") (pin "21") (pinfunction "PA11_21") (pintype "bidirectional"))
    )
    (net (code "16") (name "B_TRIG") (class "Default")
      (node (ref "Q3") (pin "C") (pinfunction "C_C") (pintype "passive"))
      (node (ref "U1") (pin "14") (pinfunction "PB0_14") (pintype "bidirectional"))
    )
    (net (code "17") (name "B_TRIG_IN") (class "Default")
      (node (ref "J2") (pin "P3") (pinfunction "3_P3") (pintype "passive"))
      (node (ref "R19") (pin "1") (pinfunction "1_1") (pintype "passive"))
    )
    (net (code "18") (name "C_ADC") (class "Default")
      (node (ref "R34") (pin "2") (pinfunction "2_2") (pintype "passive"))
      (node (ref "U1") (pin "12") (pinfunction "PA6_12") (pintype "bidirectional"))
    )
    (net (code "19") (name "C_CV") (class "Default")
      (node (ref "C24") (pin "2") (pinfunction "2_2") (pintype "passive"))
      (node (ref "R8") (pin "1") (pinfunction "1_1") (pintype "passive"))
      (node (ref "U1") (pin "8") (pinfunction "PA2_8") (pintype "bidirectional"))
      (node (ref "U2") (pin "14") (pinfunction "OUT_14") (pintype "output"))
    )
    (net (code "20") (name "C_GATE") (class "Default")
      (node (ref "R11") (pin "2") (pinfunction "2_2") (pintype "passive"))
      (node (ref "U1") (pin "22") (pinfunction "PA12_22") (pintype "bidirectional"))
    )
    (net (code "21") (name "C_TRIG") (class "Default")
      (node (ref "Q2") (pin "C") (pinfunction "C_C") (pintype "passive"))
      (node (ref "U1") (pin "15") (pinfunction "PB1_15") (pintype "bidirectional"))
    )
    (net (code "22") (name "C_TRIG_IN") (class "Default")
      (node (ref "J1") (pin "P3") (pinfunction "3_P3") (pintype "passive"))
      (node (ref "R18") (pin "1") (pinfunction "1_1") (pintype "passive"))
    )
    (net (code "23") (name "GND") (class "Default")
      (node (ref "C1") (pin "2") (pinfunction "2_2") (pintype "passive"))
      (node (ref "C10") (pin "1") (pinfunction "1_1") (pintype "passive"))
      (node (ref "C11") (pin "2") (pinfunction "2_2") (pintype "passive"))
      (node (ref "C12") (pin "2") (pinfunction "2_2") (pintype "passive"))
      (node (ref "C13") (pin "2") (pinfunction "2_2") (pintype "passive"))
      (node (ref "C14") (pin "2") (pinfunction "2_2") (pintype "passive"))
      (node (ref "C15") (pin "2") (pinfunction "2_2") (pintype "passive"))
      (node (ref "C16") (pin "2") (pinfunction "2_2") (pintype "passive"))
      (node (ref "C17") (pin "2") (pinfunction "2_2") (pintype "passive"))
      (node (ref "C18") (pin "2") (pinfunction "2_2") (pintype "passive"))
      (node (ref "C19") (pin "2") (pinfunction "2_2") (pintype "passive"))
      (node (ref "C2") (pin "2") (pinfunction "2_2") (pintype "passive"))
      (node (ref "C20") (pin "2") (pinfunction "2_2") (pintype "passive"))
      (node (ref "C21") (pin "1") (pinfunction "1_1") (pintype "passive"))
      (node (ref "C22") (pin "1") (pinfunction "1_1") (pintype "passive"))
      (node (ref "C25") (pin "1") (pinfunction "1_1") (pintype "passive"))
      (node (ref "C26") (pin "2") (pinfunction "2_2") (pintype "passive"))
      (node (ref "C27") (pin "2") (pinfunction "2_2") (pintype "passive"))
      (node (ref "C28") (pin "2") (pinfunction "2_2") (pintype "passive"))
      (node (ref "C29") (pin "2") (pinfunction "2_2") (pintype "passive"))
      (node (ref "C3") (pin "2") (pinfunction "2_2") (pintype "passive"))
      (node (ref "C31") (pin "2") (pinfunction "2_2") (pintype "passive"))
      (node (ref "C35") (pin "2") (pinfunction "2_2") (pintype "passive"))
      (node (ref "C4") (pin "2") (pinfunction "2_2") (pintype "passive"))
      (node (ref "C5") (pin "2") (pinfunction "2_2") (pintype "passive"))
      (node (ref "C6") (pin "2") (pinfunction "2_2") (pintype "passive"))
      (node (ref "C7") (pin "2") (pinfunction "2_2") (pintype "passive"))
      (node (ref "C8") (pin "-") (pinfunction "-_-") (pintype "passive"))
      (node (ref "C9") (pin "1") (pinfunction "1_1") (pintype "passive"))
      (node (ref "D3") (pin "A") (pinfunction "A_A") (pintype "passive"))
      (node (ref "D4") (pin "A") (pinfunction "A_A") (pintype "passive"))
      (node (ref "D5") (pin "A") (pinfunction "A_A") (pintype "passive"))
      (node (ref "IC1") (pin "2") (pinfunction "GND_2") (pintype "passive"))
      (node (ref "IC2") (pin "2") (pinfunction "GND_2") (pintype "passive"))
      (node (ref "IC3") (pin "1") (pinfunction "C_1") (pintype "passive"))
      (node (ref "IC4") (pin "6") (pinfunction "INH_6") (pintype "input"))
      (node (ref "IC4") (pin "7") (pinfunction "VEE_7") (pintype "power_in"))
      (node (ref "IC4") (pin "8") (pinfunction "GND_8") (pintype "power_in"))
      (node (ref "IC5") (pin "1") (pinfunction "GND_1") (pintype "bidirectional"))
      (node (ref "IC5") (pin "21") (pinfunction "BLANK_21") (pintype "bidirectional"))
      (node (ref "IC6") (pin "11") (pinfunction "V-_11") (pintype "power_in"))
      (node (ref "IC6") (pin "12") (pinfunction "+IN_12") (pintype "input"))
      (node (ref "J1") (pin "P1") (pinfunction "1_P1") (pintype "passive"))
      (node (ref "J1") (pin "P2") (pinfunction "2_P2") (pintype "passive"))
      (node (ref "J10") (pin "P1") (pinfunction "1_P1") (pintype "passive"))
      (node (ref "J11") (pin "P1") (pinfunction "1_P1") (pintype "passive"))
      (node (ref "J12") (pin "P1") (pinfunction "1_P1") (pintype "passive"))
      (node (ref "J2") (pin "P1") (pinfunction "1_P1") (pintype "passive"))
      (node (ref "J2") (pin "P2") (pinfunction "2_P2") (pintype "passive"))
      (node (ref "J3") (pin "P1") (pinfunction "1_P1") (pintype "passive"))
      (node (ref "J3") (pin "P2") (pinfunction "2_P2") (pintype "passive"))
      (node (ref "J4") (pin "P1") (pinfunction "1_P1") (pintype "passive"))
      (node (ref "J4") (pin "P2") (pinfunction "2_P2") (pintype "passive"))
      (node (ref "J5") (pin "P1") (pinfunction "1_P1") (pintype "passive"))
      (node (ref "J5") (pin "P2") (pinfunction "2_P2") (pintype "passive"))
      (node (ref "J6") (pin "P1") (pinfunction "1_P1") (pintype "passive"))
      (node (ref "J6") (pin "P2") (pinfunction "2_P2") (pintype "passive"))
      (node (ref "J7") (pin "P1") (pinfunction "1_P1") (pintype "passive"))
      (node (ref "J8") (pin "P1") (pinfunction "1_P1") (pintype "passive"))
      (node (ref "J9") (pin "P1") (pinfunction "1_P1") (pintype "passive"))
      (node (ref "JP1") (pin "3") (pinfunction "3_3") (pintype "passive"))
      (node (ref "JP1") (pin "4") (pinfunction "4_4") (pintype "passive"))
      (node (ref "JP1") (pin "5") (pinfunction "5_5") (pintype "passive"))
      (node (ref "JP1") (pin "6") (pinfunction "6_6") (pintype "passive"))
      (node (ref "JP1") (pin "7") (pinfunction "7_7") (pintype "passive"))
      (node (ref "JP1") (pin "8") (pinfunction "8_8") (pintype "passive"))
      (node (ref "JP2") (pin "1") (pinfunction "1_1") (pintype "passive"))
      (node (ref "POT_A") (pin "P$3") (pinfunction "A_P$3") (pintype "passive"))
      (node (ref "POT_B") (pin "P$3") (pinfunction "A_P$3") (pintype "passive"))
      (node (ref "POT_C") (pin "P$3") (pinfunction "A_P$3") (pintype "passive"))
      (node (ref "Q1") (pin "2") (pinfunction "LID1_2") (pintype "power_in"))
      (node (ref "Q1") (pin "4") (pinfunction "LID2_4") (pintype "power_in"))
      (node (ref "Q2") (pin "E") (pinfunction "E_E") (pintype "passive"))
      (node (ref "Q3") (pin "E") (pinfunction "E_E") (pintype "passive"))
      (node (ref "Q4") (pin "E") (pinfunction "E_E") (pintype "passive"))
      (node (ref "R20") (pin "1") (pinfunction "1_1") (pintype "passive"))
      (node (ref "R21") (pin "1") (pinfunction "1_1") (pintype "passive"))
      (node (ref "R23") (pin "1") (pinfunction "1_1") (pintype "passive"))
      (node (ref "R45") (pin "2") (pinfunction "2_2") (pintype "passive"))
      (node (ref "R46") (pin "2") (pinfunction "2_2") (pintype "passive"))
      (node (ref "R47") (pin "2") (pinfunction "2_2") (pintype "passive"))
      (node (ref "R5") (pin "2") (pinfunction "2_2") (pintype "passive"))
      (node (ref "SLD_A") (pin "1") (pinfunction "A_1") (pintype "passive"))
      (node (ref "SLD_B") (pin "1") (pinfunction "A_1") (pintype "passive"))
      (node (ref "SLD_C") (pin "1") (pinfunction "A_1") (pintype "passive"))
      (node (ref "SW_A") (pin "1") (pinfunction "1_1") (pintype "passive"))
      (node (ref "SW_A") (pin "2") (pinfunction "2_2") (pintype "passive"))
      (node (ref "SW_B") (pin "1") (pinfunction "1_1") (pintype "passive"))
      (node (ref "SW_B") (pin "2") (pinfunction "2_2") (pintype "passive"))
      (node (ref "SW_C") (pin "1") (pinfunction "1_1") (pintype "passive"))
      (node (ref "SW_C") (pin "2") (pinfunction "2_2") (pintype "passive"))
      (node (ref "U$1") (pin "6") (pinfunction "P$6_6") (pintype "bidirectional"))
      (node (ref "U1") (pin "16") (pinfunction "VSS_2_16") (pintype "power_in"))
      (node (ref "U1") (pin "31") (pinfunction "BOOT0_31") (pintype "input"))
      (node (ref "U1") (pin "32") (pinfunction "VSS_1_32") (pintype "power_in"))
      (node (ref "U2") (pin "10") (pinfunction "+IN_10") (pintype "input"))
      (node (ref "U2") (pin "11") (pinfunction "V-_11") (pintype "power_in"))
      (node (ref "U2") (pin "12") (pinfunction "+IN_12") (pintype "input"))
      (node (ref "U2") (pin "3") (pinfunction "+IN_3") (pintype "input"))
      (node (ref "U2") (pin "5") (pinfunction "+IN_5") (pintype "input"))
      (node (ref "U3") (pin "10") (pinfunction "+IN_10") (pintype "input"))
      (node (ref "U3") (pin "12") (pinfunction "+IN_12") (pintype "input"))
      (node (ref "U3") (pin "3") (pinfunction "+IN_3") (pintype "input"))
      (node (ref "U3") (pin "5") (pinfunction "+IN_5") (pintype "input"))
    )
    (net (code "24") (name "LEDS_SCK") (class "Default")
      (node (ref "IC5") (pin "3") (pinfunction "SCLK_3") (pintype "bidirectional"))
      (node (ref "U1") (pin "26") (pinfunction "PB3_26") (pintype "bidirectional"))
    )
    (net (code "25") (name "LEDS_SIN") (class "Default")
      (node (ref "IC5") (pin "2") (pinfunction "SIN_2") (pintype "bidirectional"))
      (node (ref "U1") (pin "28") (pinfunction "PB5_28") (pintype "bidirectional"))
    )
    (net (code "26") (name "N_U") (class "Default")
      (node (ref "U2") (pin "6") (pinfunction "-IN_6") (pintype "input"))
      (node (ref "U2") (pin "7") (pinfunction "OUT_7") (pintype "output"))
    )
    (net (code "27") (name "Net-(A-GRN)") (class "Default")
      (node (ref "A") (pin "GREEN_C") (pinfunction "GRN_GREEN_C") (pintype "bidirectional"))
      (node (ref "IC5") (pin "9") (pinfunction "OUT4_9") (pintype "bidirectional"))
    )
    (net (code "28") (name "Net-(A-RED)") (class "Default")
      (node (ref "A") (pin "RED_C") (pinfunction "RED_RED_C") (pintype "bidirectional"))
      (node (ref "IC5") (pin "10") (pinfunction "OUT5_10") (pintype "bidirectional"))
    )
    (net (code "29") (name "Net-(A_OUT-GRN)") (class "Default")
      (node (ref "A_OUT") (pin "GREEN_C") (pinfunction "GRN_GREEN_C") (pintype "bidirectional"))
      (node (ref "IC5") (pin "13") (pinfunction "OUT8_13") (pintype "bidirectional"))
    )
    (net (code "30") (name "Net-(A_OUT-RED)") (class "Default")
      (node (ref "A_OUT") (pin "RED_C") (pinfunction "RED_RED_C") (pintype "bidirectional"))
      (node (ref "IC5") (pin "14") (pinfunction "OUT9_14") (pintype "bidirectional"))
    )
    (net (code "31") (name "Net-(B-GRN)") (class "Default")
      (node (ref "B") (pin "GREEN_C") (pinfunction "GRN_GREEN_C") (pintype "bidirectional"))
      (node (ref "IC5") (pin "11") (pinfunction "OUT6_11") (pintype "bidirectional"))
    )
    (net (code "32") (name "Net-(B-RED)") (class "Default")
      (node (ref "B") (pin "RED_C") (pinfunction "RED_RED_C") (pintype "bidirectional"))
      (node (ref "IC5") (pin "12") (pinfunction "OUT7_12") (pintype "bidirectional"))
    )
    (net (code "33") (name "Net-(B_OUT-GRN)") (class "Default")
      (node (ref "B_OUT") (pin "GREEN_C") (pinfunction "GRN_GREEN_C") (pintype "bidirectional"))
      (node (ref "IC5") (pin "16") (pinfunction "OUT11_16") (pintype "bidirectional"))
    )
    (net (code "34") (name "Net-(B_OUT-RED)") (class "Default")
      (node (ref "B_OUT") (pin "RED_C") (pinfunction "RED_RED_C") (pintype "bidirectional"))
      (node (ref "IC5") (pin "15") (pinfunction "OUT10_15") (pintype "bidirectional"))
    )
    (net (code "35") (name "Net-(C-GRN)") (class "Default")
      (node (ref "C") (pin "GREEN_C") (pinfunction "GRN_GREEN_C") (pintype "bidirectional"))
      (node (ref "IC5") (pin "8") (pinfunction "OUT3_8") (pintype "bidirectional"))
    )
    (net (code "36") (name "Net-(C-RED)") (class "Default")
      (node (ref "C") (pin "RED_C") (pinfunction "RED_RED_C") (pintype "bidirectional"))
      (node (ref "IC5") (pin "7") (pinfunction "OUT2_7") (pintype "bidirectional"))
    )
    (net (code "37") (name "Net-(C1-Pad1)") (class "Default")
      (node (ref "C1") (pin "1") (pinfunction "1_1") (pintype "passive"))
      (node (ref "D1") (pin "C") (pinfunction "C_C") (pintype "passive"))
      (node (ref "L1") (pin "1") (pinfunction "1_1") (pintype "passive"))
      (node (ref "L2") (pin "2") (pinfunction "2_2") (pintype "passive"))
      (node (ref "L3") (pin "2") (pinfunction "2_2") (pintype "passive"))
    )
    (net (code "38") (name "Net-(C22-Pad2)") (class "Default")
      (node (ref "C22") (pin "2") (pinfunction "2_2") (pintype "passive"))
      (node (ref "Q1") (pin "1") (pinfunction "1_1") (pintype "passive"))
      (node (ref "R6") (pin "2") (pinfunction "2_2") (pintype "passive"))
    )
    (net (code "39") (name "Net-(C_OUT-GRN)") (class "Default")
      (node (ref "C_OUT") (pin "GREEN_C") (pinfunction "GRN_GREEN_C") (pintype "bidirectional"))
      (node (ref "IC5") (pin "18") (pinfunction "OUT13_18") (pintype "bidirectional"))
    )
    (net (code "40") (name "Net-(C_OUT-RED)") (class "Default")
      (node (ref "C_OUT") (pin "RED_C") (pinfunction "RED_RED_C") (pintype "bidirectional"))
      (node (ref "IC5") (pin "17") (pinfunction "OUT12_17") (pintype "bidirectional"))
    )
    (net (code "41") (name "Net-(D2-PadA)") (class "Default")
      (node (ref "D2") (pin "A") (pinfunction "A_A") (pintype "passive"))
      (node (ref "L4") (pin "2") (pinfunction "2_2") (pintype "passive"))
    )
    (net (code "42") (name "Net-(D3-PadC)") (class "Default")
      (node (ref "D3") (pin "C") (pinfunction "C_C") (pintype "passive"))
      (node (ref "Q2") (pin "B") (pinfunction "B_B") (pintype "passive"))
      (node (ref "R18") (pin "2") (pinfunction "2_2") (pintype "passive"))
      (node (ref "R23") (pin "2") (pinfunction "2_2") (pintype "passive"))
    )
    (net (code "43") (name "Net-(D4-PadC)") (class "Default")
      (node (ref "D4") (pin "C") (pinfunction "C_C") (pintype "passive"))
      (node (ref "Q3") (pin "B") (pinfunction "B_B") (pintype "passive"))
      (node (ref "R19") (pin "2") (pinfunction "2_2") (pintype "passive"))
      (node (ref "R20") (pin "2") (pinfunction "2_2") (pintype "passive"))
    )
    (net (code "44") (name "Net-(D5-PadC)") (class "Default")
      (node (ref "D5") (pin "C") (pinfunction "C_C") (pintype "passive"))
      (node (ref "Q4") (pin "B") (pinfunction "B_B") (pintype "passive"))
      (node (ref "R21") (pin "2") (pinfunction "2_2") (pintype "passive"))
      (node (ref "R22") (pin "2") (pinfunction "2_2") (pintype "passive"))
    )
    (net (code "45") (name "Net-(IC1-VI)") (class "Default")
      (node (ref "C5") (pin "1") (pinfunction "1_1") (pintype "passive"))
      (node (ref "IC1") (pin "1") (pinfunction "VI_1") (pintype "input"))
      (node (ref "L1") (pin "2") (pinfunction "2_2") (pintype "passive"))
    )
    (net (code "46") (name "Net-(IC2-VI)") (class "Default")
      (node (ref "C3") (pin "1") (pinfunction "1_1") (pintype "passive"))
      (node (ref "IC2") (pin "3") (pinfunction "VI_3") (pintype "input"))
      (node (ref "L2") (pin "1") (pinfunction "1_1") (pintype "passive"))
    )
    (net (code "47") (name "Net-(IC4A-X0)") (class "Default")
      (node (ref "IC4") (pin "13") (pinfunction "X0_13") (pintype "bidirectional"))
      (node (ref "POT_C") (pin "P$2") (pinfunction "S_P$2") (pintype "passive"))
    )
    (net (code "48") (name "Net-(IC4A-X1)") (class "Default")
      (node (ref "IC4") (pin "14") (pinfunction "X1_14") (pintype "bidirectional"))
      (node (ref "SLD_C") (pin "2") (pinfunction "S_2") (pintype "passive"))
    )
    (net (code "49") (name "Net-(IC4A-X2)") (class "Default")
      (node (ref "IC4") (pin "15") (pinfunction "X2_15") (pintype "bidirectional"))
      (node (ref "SLD_B") (pin "2") (pinfunction "S_2") (pintype "passive"))
    )
    (net (code "50") (name "Net-(IC4A-X3)") (class "Default")
      (node (ref "IC4") (pin "12") (pinfunction "X3_12") (pintype "bidirectional"))
      (node (ref "POT_A") (pin "P$2") (pinfunction "S_P$2") (pintype "passive"))
    )
    (net (code "51") (name "Net-(IC4A-X4)") (class "Default")
      (node (ref "IC4") (pin "1") (pinfunction "X4_1") (pintype "bidirectional"))
      (node (ref "SLD_A") (pin "2") (pinfunction "S_2") (pintype "passive"))
    )
    (net (code "52") (name "Net-(IC4A-X6)") (class "Default")
      (node (ref "IC4") (pin "2") (pinfunction "X6_2") (pintype "bidirectional"))
      (node (ref "POT_B") (pin "P$2") (pinfunction "S_P$2") (pintype "passive"))
    )
    (net (code "53") (name "Net-(IC5-IREF)") (class "Default")
      (node (ref "IC5") (pin "23") (pinfunction "IREF_23") (pintype "bidirectional"))
      (node (ref "R5") (pin "1") (pinfunction "1_1") (pintype "passive"))
    )
    (net (code "54") (name "Net-(IC5-OUT1)") (class "Default")
      (node (ref "IC5") (pin "6") (pinfunction "OUT1_6") (pintype "bidirectional"))
      (node (ref "R15") (pin "2") (pinfunction "2_2") (pintype "passive"))
    )
    (net (code "55") (name "Net-(IC5-OUT14)") (class "Default")
      (node (ref "IC5") (pin "19") (pinfunction "OUT14_19") (pintype "bidirectional"))
      (node (ref "R16") (pin "2") (pinfunction "2_2") (pintype "passive"))
    )
    (net (code "56") (name "Net-(IC5-OUT15)") (class "Default")
      (node (ref "IC5") (pin "20") (pinfunction "OUT15_20") (pintype "bidirectional"))
      (node (ref "R17") (pin "2") (pinfunction "2_2") (pintype "passive"))
    )
    (net (code "57") (name "Net-(IC5-VCC)") (class "Default")
      (node (ref "C14") (pin "1") (pinfunction "1_1") (pintype "passive"))
      (node (ref "C15") (pin "1") (pinfunction "1_1") (pintype "passive"))
      (node (ref "IC5") (pin "24") (pinfunction "VCC_24") (pintype "bidirectional"))
      (node (ref "L5") (pin "1") (pinfunction "1_1") (pintype "passive"))
    )
    (net (code "58") (name "Net-(IC6A-+IN)") (class "Default")
      (node (ref "IC6") (pin "3") (pinfunction "+IN_3") (pintype "input"))
      (node (ref "R44") (pin "2") (pinfunction "2_2") (pintype "passive"))
      (node (ref "R47") (pin "1") (pinfunction "1_1") (pintype "passive"))
    )
    (net (code "59") (name "Net-(IC6A--IN)") (class "Default")
      (node (ref "IC6") (pin "2") (pinfunction "-IN_2") (pintype "input"))
      (node (ref "R13") (pin "1") (pinfunction "1_1") (pintype "passive"))
    )
    (net (code "60") (name "Net-(IC6A-OUT)") (class "Default")
      (node (ref "IC6") (pin "1") (pinfunction "OUT_1") (pintype "output"))
      (node (ref "R39") (pin "2") (pinfunction "2_2") (pintype "passive"))
      (node (ref "R44") (pin "1") (pinfunction "1_1") (pintype "passive"))
    )
    (net (code "61") (name "Net-(IC6B-+IN)") (class "Default")
      (node (ref "IC6") (pin "5") (pinfunction "+IN_5") (pintype "input"))
      (node (ref "R41") (pin "2") (pinfunction "2_2") (pintype "passive"))
      (node (ref "R46") (pin "1") (pinfunction "1_1") (pintype "passive"))
    )
    (net (code "62") (name "Net-(IC6B--IN)") (class "Default")
      (node (ref "IC6") (pin "6") (pinfunction "-IN_6") (pintype "input"))
      (node (ref "R12") (pin "1") (pinfunction "1_1") (pintype "passive"))
    )
    (net (code "63") (name "Net-(IC6B-OUT)") (class "Default")
      (node (ref "IC6") (pin "7") (pinfunction "OUT_7") (pintype "output"))
      (node (ref "R38") (pin "2") (pinfunction "2_2") (pintype "passive"))
      (node (ref "R41") (pin "1") (pinfunction "1_1") (pintype "passive"))
    )
    (net (code "64") (name "Net-(IC6C-+IN)") (class "Default")
      (node (ref "IC6") (pin "10") (pinfunction "+IN_10") (pintype "input"))
      (node (ref "R36") (pin "2") (pinfunction "2_2") (pintype "passive"))
      (node (ref "R45") (pin "1") (pinfunction "1_1") (pintype "passive"))
    )
    (net (code "65") (name "Net-(IC6C--IN)") (class "Default")
      (node (ref "IC6") (pin "9") (pinfunction "-IN_9") (pintype "input"))
      (node (ref "R11") (pin "1") (pinfunction "1_1") (pintype "passive"))
    )
    (net (code "66") (name "Net-(IC6C-OUT)") (class "Default")
      (node (ref "IC6") (pin "8") (pinfunction "OUT_8") (pintype "output"))
      (node (ref "R36") (pin "1") (pinfunction "1_1") (pintype "passive"))
      (node (ref "R37") (pin "2") (pinfunction "2_2") (pintype "passive"))
    )
    (net (code "67") (name "Net-(IC6D--IN)") (class "Default")
      (node (ref "IC6") (pin "13") (pinfunction "-IN_13") (pintype "input"))
      (node (ref "IC6") (pin "14") (pinfunction "OUT_14") (pintype "output"))
    )
    (net (code "68") (name "Net-(J4-3)") (class "Default")
      (node (ref "J4") (pin "P3") (pinfunction "3_P3") (pintype "passive"))
      (node (ref "R24") (pin "2") (pinfunction "2_2") (pintype "passive"))
    )
    (net (code "69") (name "Net-(J6-3)") (class "Default")
      (node (ref "J6") (pin "P3") (pinfunction "3_P3") (pintype "passive"))
      (node (ref "R26") (pin "2") (pinfunction "2_2") (pintype "passive"))
    )
    (net (code "70") (name "Net-(J7-3)") (class "Default")
      (node (ref "J7") (pin "P3") (pinfunction "3_P3") (pintype "passive"))
      (node (ref "R37") (pin "1") (pinfunction "1_1") (pintype "passive"))
    )
    (net (code "71") (name "Net-(J8-3)") (class "Default")
      (node (ref "J8") (pin "P3") (pinfunction "3_P3") (pintype "passive"))
      (node (ref "R38") (pin "1") (pinfunction "1_1") (pintype "passive"))
    )
    (net (code "72") (name "Net-(J9-3)") (class "Default")
      (node (ref "J9") (pin "P3") (pinfunction "3_P3") (pintype "passive"))
      (node (ref "R39") (pin "1") (pinfunction "1_1") (pintype "passive"))
    )
    (net (code "73") (name "Net-(J10-3)") (class "Default")
      (node (ref "J10") (pin "P3") (pinfunction "3_P3") (pintype "passive"))
      (node (ref "R35") (pin "1") (pinfunction "1_1") (pintype "passive"))
      (node (ref "R40") (pin "1") (pinfunction "1_1") (pintype "passive"))
    )
    (net (code "74") (name "Net-(J11-3)") (class "Default")
      (node (ref "J11") (pin "P3") (pinfunction "3_P3") (pintype "passive"))
      (node (ref "R29") (pin "1") (pinfunction "1_1") (pintype "passive"))
      (node (ref "R42") (pin "1") (pinfunction "1_1") (pintype "passive"))
    )
    (net (code "75") (name "Net-(J12-3)") (class "Default")
      (node (ref "J12") (pin "P3") (pinfunction "3_P3") (pintype "passive"))
      (node (ref "R32") (pin "1") (pinfunction "1_1") (pintype "passive"))
      (node (ref "R43") (pin "1") (pinfunction "1_1") (pintype "passive"))
    )
    (net (code "76") (name "Net-(Q1B-2)") (class "Default")
      (node (ref "C21") (pin "2") (pinfunction "2_2") (pintype "passive"))
      (node (ref "Q1") (pin "3") (pinfunction "2_3") (pintype "passive"))
      (node (ref "R9") (pin "2") (pinfunction "2_2") (pintype "passive"))
    )
    (net (code "77") (name "Net-(SLD_AA-C)") (class "Default")
      (node (ref "R16") (pin "1") (pinfunction "1_1") (pintype "passive"))
      (node (ref "SLD_A") (pin "E") (pinfunction "C_E") (pintype "passive"))
    )
    (net (code "78") (name "Net-(SLD_BA-C)") (class "Default")
      (node (ref "R17") (pin "1") (pinfunction "1_1") (pintype "passive"))
      (node (ref "SLD_B") (pin "E") (pinfunction "C_E") (pintype "passive"))
    )
    (net (code "79") (name "Net-(SLD_CA-C)") (class "Default")
      (node (ref "R15") (pin "1") (pinfunction "1_1") (pintype "passive"))
      (node (ref "SLD_C") (pin "E") (pinfunction "C_E") (pintype "passive"))
    )
    (net (code "80") (name "Net-(U1-PF0{slash}OSC_IN)") (class "Default")
      (node (ref "R9") (pin "1") (pinfunction "1_1") (pintype "passive"))
      (node (ref "U1") (pin "2") (pinfunction "PF0/OSC_IN_2") (pintype "bidirectional"))
    )
    (net (code "81") (name "Net-(U1-PF1{slash}OSC_OUT)") (class "Default")
      (node (ref "R6") (pin "1") (pinfunction "1_1") (pintype "passive"))
      (node (ref "U1") (pin "3") (pinfunction "PF1/OSC_OUT_3") (pintype "bidirectional"))
    )
    (net (code "82") (name "Net-(U2A--IN)") (class "Default")
      (node (ref "C30") (pin "1") (pinfunction "1_1") (pintype "passive"))
      (node (ref "R14") (pin "2") (pinfunction "2_2") (pintype "passive"))
      (node (ref "R2") (pin "1") (pinfunction "1_1") (pintype "passive"))
      (node (ref "R26") (pin "1") (pinfunction "1_1") (pintype "passive"))
      (node (ref "U2") (pin "2") (pinfunction "-IN_2") (pintype "input"))
    )
    (net (code "83") (name "Net-(U2C--IN)") (class "Default")
      (node (ref "C23") (pin "1") (pinfunction "1_1") (pintype "passive"))
      (node (ref "R25") (pin "1") (pinfunction "1_1") (pintype "passive"))
      (node (ref "R3") (pin "1") (pinfunction "1_1") (pintype "passive"))
      (node (ref "R7") (pin "2") (pinfunction "2_2") (pintype "passive"))
      (node (ref "U2") (pin "9") (pinfunction "-IN_9") (pintype "input"))
    )
    (net (code "84") (name "Net-(U2D--IN)") (class "Default")
      (node (ref "C24") (pin "1") (pinfunction "1_1") (pintype "passive"))
      (node (ref "R24") (pin "1") (pinfunction "1_1") (pintype "passive"))
      (node (ref "R4") (pin "1") (pinfunction "1_1") (pintype "passive"))
      (node (ref "R8") (pin "2") (pinfunction "2_2") (pintype "passive"))
      (node (ref "U2") (pin "13") (pinfunction "-IN_13") (pintype "input"))
    )
    (net (code "85") (name "Net-(U3A--IN)") (class "Default")
      (node (ref "C33") (pin "1") (pinfunction "1_1") (pintype "passive"))
      (node (ref "R30") (pin "1") (pinfunction "1_1") (pintype "passive"))
      (node (ref "R31") (pin "1") (pinfunction "1_1") (pintype "passive"))
      (node (ref "R32") (pin "2") (pinfunction "2_2") (pintype "passive"))
      (node (ref "U3") (pin "2") (pinfunction "-IN_2") (pintype "input"))
    )
    (net (code "86") (name "Net-(U3A-OUT)") (class "Default")
      (node (ref "C33") (pin "2") (pinfunction "2_2") (pintype "passive"))
      (node (ref "R43") (pin "2") (pinfunction "2_2") (pintype "passive"))
      (node (ref "U3") (pin "1") (pinfunction "OUT_1") (pintype "output"))
    )
    (net (code "87") (name "Net-(U3B--IN)") (class "Default")
      (node (ref "C32") (pin "1") (pinfunction "1_1") (pintype "passive"))
      (node (ref "R27") (pin "1") (pinfunction "1_1") (pintype "passive"))
      (node (ref "R28") (pin "1") (pinfunction "1_1") (pintype "passive"))
      (node (ref "R29") (pin "2") (pinfunction "2_2") (pintype "passive"))
      (node (ref "U3") (pin "6") (pinfunction "-IN_6") (pintype "input"))
    )
    (net (code "88") (name "Net-(U3B-OUT)") (class "Default")
      (node (ref "C32") (pin "2") (pinfunction "2_2") (pintype "passive"))
      (node (ref "R42") (pin "2") (pinfunction "2_2") (pintype "passive"))
      (node (ref "U3") (pin "7") (pinfunction "OUT_7") (pintype "output"))
    )
    (net (code "89") (name "Net-(U3C--IN)") (class "Default")
      (node (ref "C34") (pin "1") (pinfunction "1_1") (pintype "passive"))
      (node (ref "R33") (pin "1") (pinfunction "1_1") (pintype "passive"))
      (node (ref "R34") (pin "1") (pinfunction "1_1") (pintype "passive"))
      (node (ref "R35") (pin "2") (pinfunction "2_2") (pintype "passive"))
      (node (ref "U3") (pin "9") (pinfunction "-IN_9") (pintype "input"))
    )
    (net (code "90") (name "Net-(U3C-OUT)") (class "Default")
      (node (ref "C34") (pin "2") (pinfunction "2_2") (pintype "passive"))
      (node (ref "R40") (pin "2") (pinfunction "2_2") (pintype "passive"))
      (node (ref "U3") (pin "8") (pinfunction "OUT_8") (pintype "output"))
    )
    (net (code "91") (name "Net-(U3D--IN)") (class "Default")
      (node (ref "U3") (pin "13") (pinfunction "-IN_13") (pintype "input"))
      (node (ref "U3") (pin "14") (pinfunction "OUT_14") (pintype "output"))
    )
    (net (code "92") (name "POTS_ADDR_A") (class "Default")
      (node (ref "IC4") (pin "11") (pinfunction "A_11") (pintype "input"))
      (node (ref "U1") (pin "13") (pinfunction "PA7_13") (pintype "bidirectional"))
    )
    (net (code "93") (name "POTS_ADDR_B") (class "Default")
      (node (ref "IC4") (pin "10") (pinfunction "B_10") (pintype "input"))
      (node (ref "U1") (pin "18") (pinfunction "PA8_18") (pintype "bidirectional"))
    )
    (net (code "94") (name "POTS_ADDR_C") (class "Default")
      (node (ref "IC4") (pin "9") (pinfunction "C_9") (pintype "input"))
      (node (ref "U1") (pin "19") (pinfunction "PA9_19") (pintype "bidirectional"))
    )
    (net (code "95") (name "RESET") (class "Default")
      (node (ref "C28") (pin "1") (pinfunction "1_1") (pintype "passive"))
      (node (ref "JP2") (pin "4") (pinfunction "4_4") (pintype "passive"))
      (node (ref "R10") (pin "2") (pinfunction "2_2") (pintype "passive"))
      (node (ref "U1") (pin "4") (pinfunction "NRST_4") (pintype "bidirectional"))
    )
    (net (code "96") (name "SWCLK") (class "Default")
      (node (ref "JP2") (pin "3") (pinfunction "3_3") (pintype "passive"))
      (node (ref "U1") (pin "24") (pinfunction "PA14_24") (pintype "bidirectional"))
    )
    (net (code "97") (name "SWDIO") (class "Default")
      (node (ref "JP2") (pin "2") (pinfunction "2_2") (pintype "passive"))
      (node (ref "U1") (pin "23") (pinfunction "PA13_23") (pintype "bidirectional"))
    )
    (net (code "98") (name "SW_MODE_A") (class "Default")
      (node (ref "SW_A") (pin "3") (pinfunction "3_3") (pintype "passive"))
      (node (ref "SW_A") (pin "4") (pinfunction "4_4") (pintype "passive"))
      (node (ref "U1") (pin "27") (pinfunction "PB4_27") (pintype "bidirectional"))
    )
    (net (code "99") (name "SW_MODE_B") (class "Default")
      (node (ref "SW_B") (pin "3") (pinfunction "3_3") (pintype "passive"))
      (node (ref "SW_B") (pin "4") (pinfunction "4_4") (pintype "passive"))
      (node (ref "U1") (pin "29") (pinfunction "PB6_29") (pintype "bidirectional"))
    )
    (net (code "100") (name "SW_MODE_C") (class "Default")
      (node (ref "SW_C") (pin "3") (pinfunction "3_3") (pintype "passive"))
      (node (ref "SW_C") (pin "4") (pinfunction "4_4") (pintype "passive"))
      (node (ref "U1") (pin "30") (pinfunction "PB7_30") (pintype "bidirectional"))
    )
    (net (code "101") (name "VCC") (class "Default")
      (node (ref "C2") (pin "1") (pinfunction "1_1") (pintype "passive"))
      (node (ref "C31") (pin "1") (pinfunction "1_1") (pintype "passive"))
      (node (ref "C35") (pin "1") (pinfunction "1_1") (pintype "passive"))
      (node (ref "C4") (pin "1") (pinfunction "1_1") (pintype "passive"))
      (node (ref "IC6") (pin "4") (pinfunction "V+_4") (pintype "power_in"))
      (node (ref "L3") (pin "1") (pinfunction "1_1") (pintype "passive"))
      (node (ref "U$1") (pin "1") (pinfunction "P$1_1") (pintype "bidirectional"))
      (node (ref "U3") (pin "4") (pinfunction "V+_4") (pintype "power_in"))
    )
    (net (code "102") (name "VEE") (class "Default")
      (node (ref "C10") (pin "2") (pinfunction "2_2") (pintype "passive"))
      (node (ref "C25") (pin "2") (pinfunction "2_2") (pintype "passive"))
      (node (ref "C9") (pin "2") (pinfunction "2_2") (pintype "passive"))
      (node (ref "L4") (pin "1") (pinfunction "1_1") (pintype "passive"))
      (node (ref "R1") (pin "1") (pinfunction "1_1") (pintype "passive"))
      (node (ref "U$1") (pin "2") (pinfunction "P$2_2") (pintype "bidirectional"))
      (node (ref "U3") (pin "11") (pinfunction "V-_11") (pintype "power_in"))
    )
    (net (code "103") (name "unconnected-(IC4A-X5-Pad5)") (class "Default")
      (node (ref "IC4") (pin "5") (pinfunction "X5_5") (pintype "bidirectional"))
    )
    (net (code "104") (name "unconnected-(IC4A-X7-Pad4)") (class "Default")
      (node (ref "IC4") (pin "4") (pinfunction "X7_4") (pintype "bidirectional"))
    )
    (net (code "105") (name "unconnected-(IC5-LAT-Pad4)") (class "Default")
      (node (ref "IC5") (pin "4") (pinfunction "LAT_4") (pintype "bidirectional"))
    )
    (net (code "106") (name "unconnected-(IC5-OUT0-Pad5)") (class "Default")
      (node (ref "IC5") (pin "5") (pinfunction "OUT0_5") (pintype "bidirectional"))
    )
    (net (code "107") (name "unconnected-(IC5-SOUT-Pad22)") (class "Default")
      (node (ref "IC5") (pin "22") (pinfunction "SOUT_22") (pintype "bidirectional"))
    )
    (net (code "108") (name "unconnected-(J7-2-PadP2)") (class "Default")
      (node (ref "J7") (pin "P2") (pinfunction "2_P2") (pintype "passive"))
    )
    (net (code "109") (name "unconnected-(J8-2-PadP2)") (class "Default")
      (node (ref "J8") (pin "P2") (pinfunction "2_P2") (pintype "passive"))
    )
    (net (code "110") (name "unconnected-(J9-2-PadP2)") (class "Default")
      (node (ref "J9") (pin "P2") (pinfunction "2_P2") (pintype "passive"))
    )
    (net (code "111") (name "unconnected-(J10-2-PadP2)") (class "Default")
      (node (ref "J10") (pin "P2") (pinfunction "2_P2") (pintype "passive"))
    )
    (net (code "112") (name "unconnected-(J11-2-PadP2)") (class "Default")
      (node (ref "J11") (pin "P2") (pinfunction "2_P2") (pintype "passive"))
    )
    (net (code "113") (name "unconnected-(J12-2-PadP2)") (class "Default")
      (node (ref "J12") (pin "P2") (pinfunction "2_P2") (pintype "passive"))
    )
  )
)
